# LPC_1.net
KiCad netlist of a schematic drawn in EAGLE
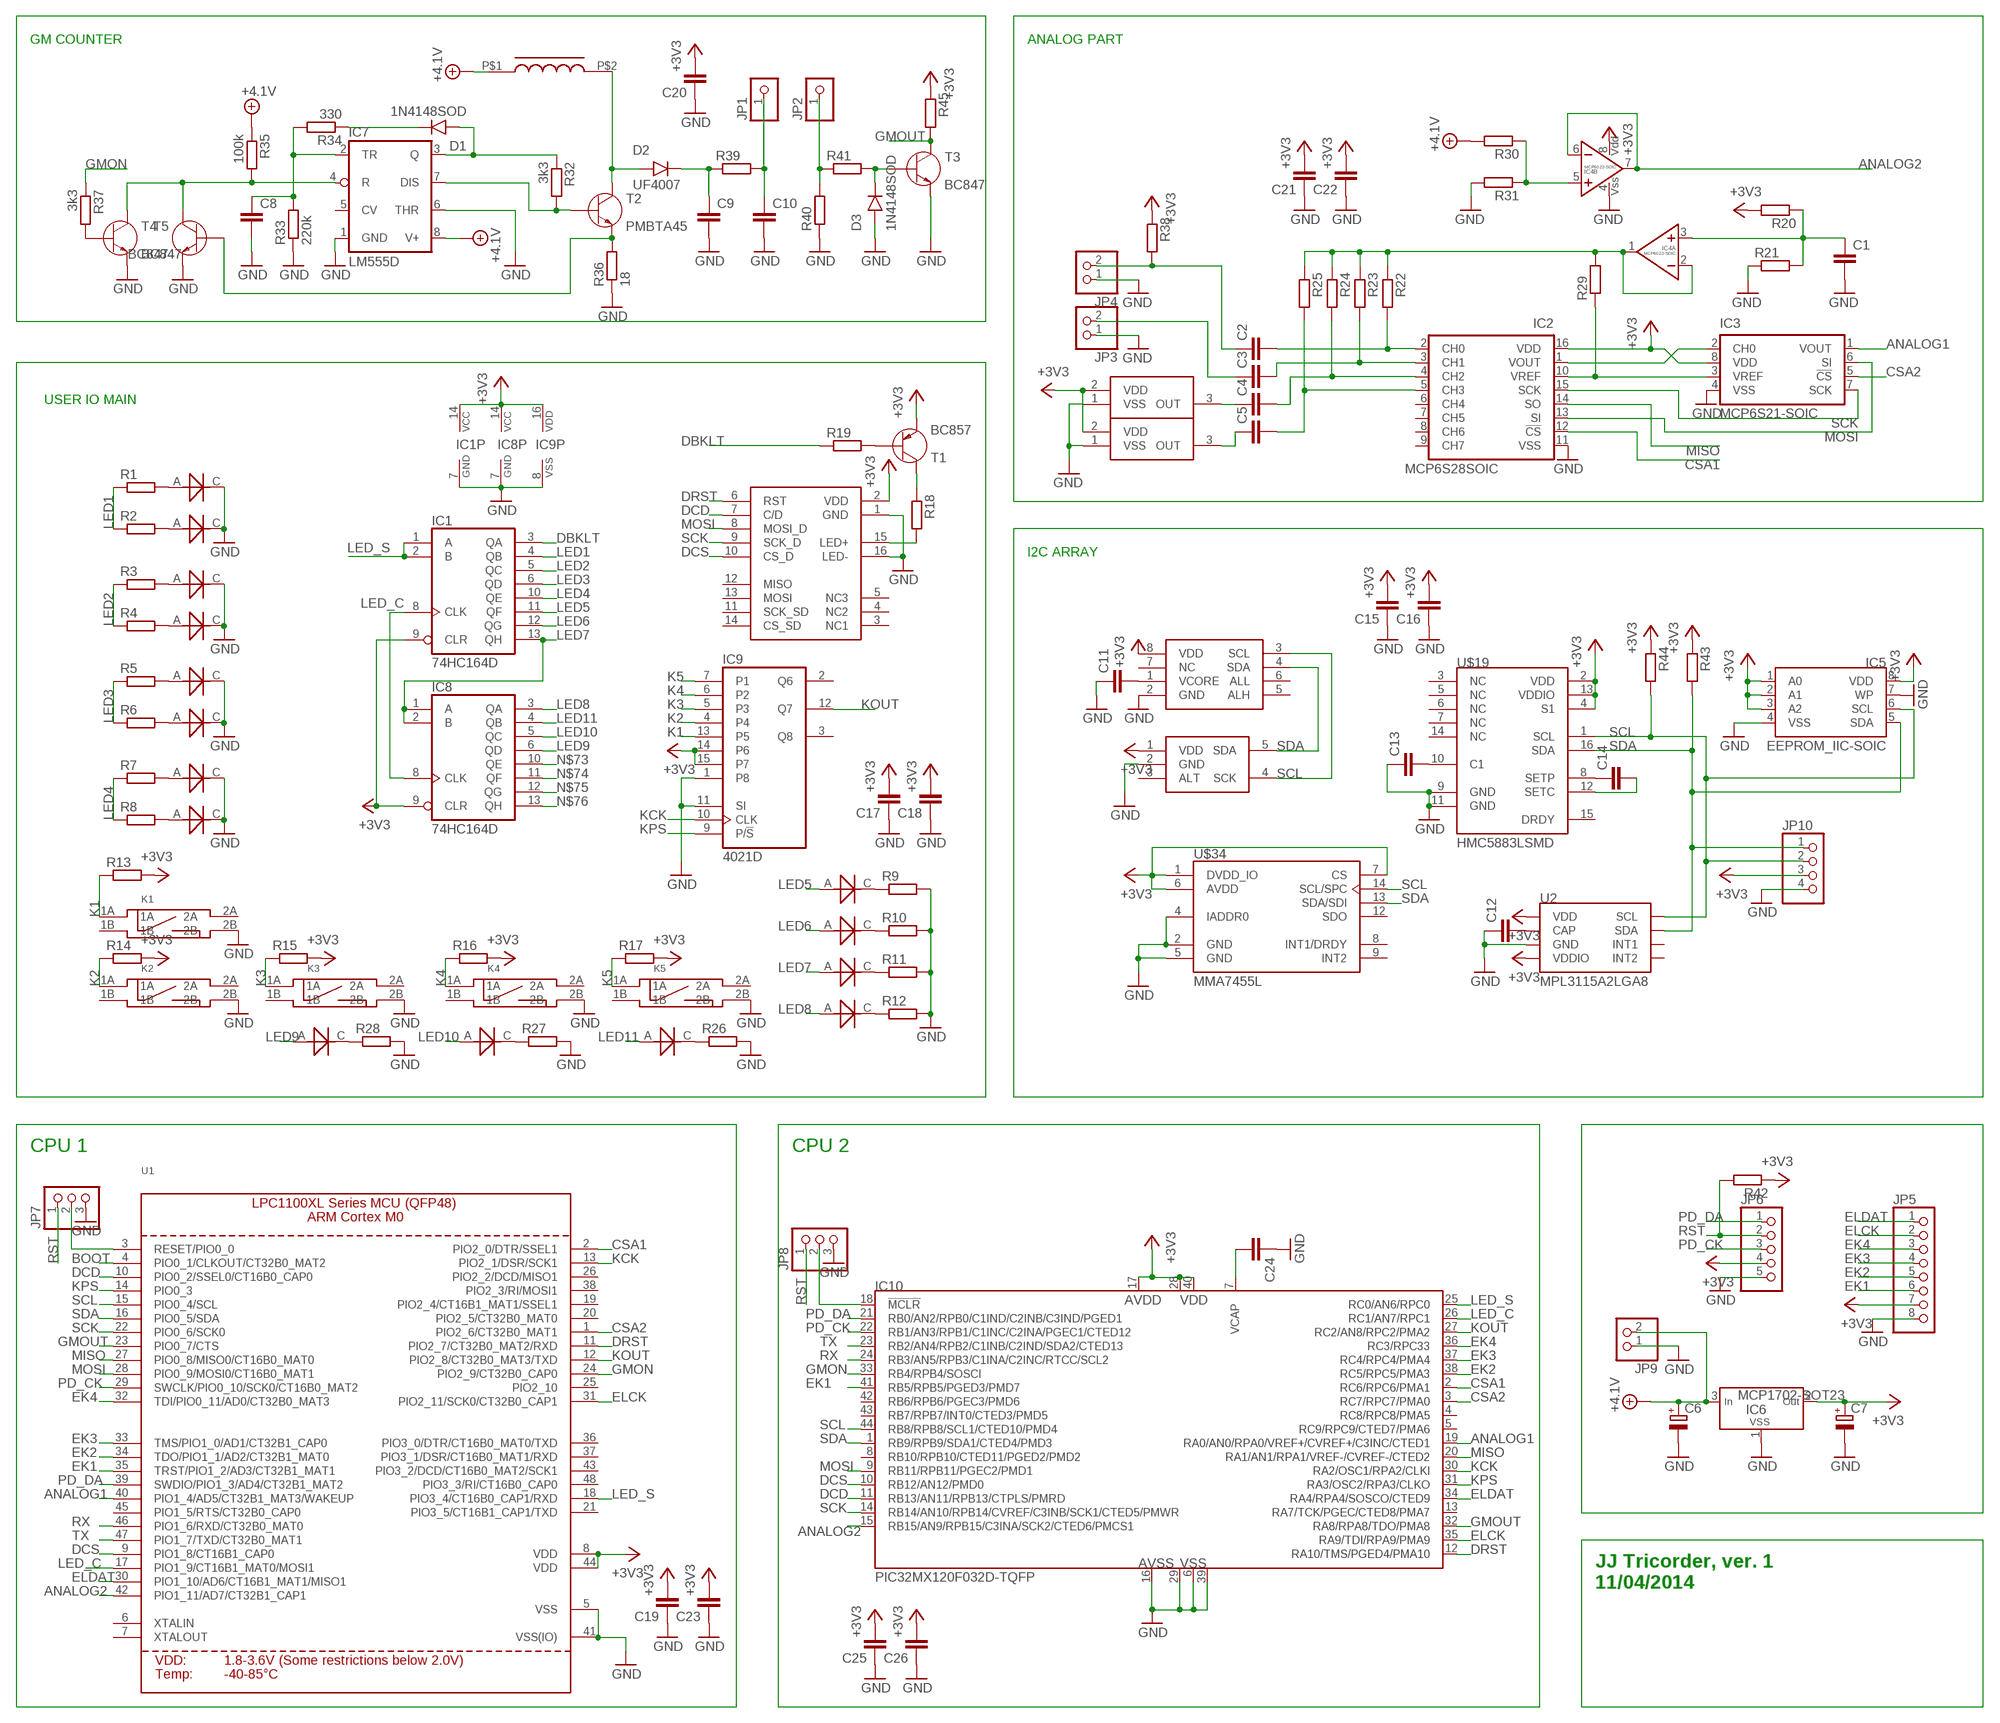
[diagram p0: schematic, sheet 1]

(export (version "E")
  (design (tool "Eeschema 10.0.6"))
  (components
    (comp (ref "C1")
      (value "C_0806")
      (footprint "eagle-import:R0805")
      (libsource (lib "eagle-import") (part "C_0806"))
    )
    (comp (ref "C2")
      (value "C_1206")
      (footprint "eagle-import:R1206")
      (libsource (lib "eagle-import") (part "C_1206"))
    )
    (comp (ref "C3")
      (value "C_1206")
      (footprint "eagle-import:R1206")
      (libsource (lib "eagle-import") (part "C_1206"))
    )
    (comp (ref "C4")
      (value "C_1206")
      (footprint "eagle-import:R1206")
      (libsource (lib "eagle-import") (part "C_1206"))
    )
    (comp (ref "C5")
      (value "C_1206")
      (footprint "eagle-import:R1206")
      (libsource (lib "eagle-import") (part "C_1206"))
    )
    (comp (ref "C6")
      (value "CPOL-EUSMCA")
      (footprint "eagle-import:SMC_A")
      (libsource (lib "eagle-import") (part "CPOL-EUSMCA"))
    )
    (comp (ref "C7")
      (value "CPOL-EUSMCA")
      (footprint "eagle-import:SMC_A")
      (libsource (lib "eagle-import") (part "CPOL-EUSMCA"))
    )
    (comp (ref "C8")
      (value "C_0806")
      (footprint "eagle-import:R0805")
      (libsource (lib "eagle-import") (part "C_0806"))
    )
    (comp (ref "C9")
      (value "C_1206")
      (footprint "eagle-import:R1206")
      (libsource (lib "eagle-import") (part "C_1206"))
    )
    (comp (ref "C10")
      (value "C_1206")
      (footprint "eagle-import:R1206")
      (libsource (lib "eagle-import") (part "C_1206"))
    )
    (comp (ref "C11")
      (value "C_0806")
      (footprint "eagle-import:R0805")
      (libsource (lib "eagle-import") (part "C_0806"))
    )
    (comp (ref "C12")
      (value "C_0806")
      (footprint "eagle-import:R0805")
      (libsource (lib "eagle-import") (part "C_0806"))
    )
    (comp (ref "C13")
      (value "C_0806")
      (footprint "eagle-import:R0805")
      (libsource (lib "eagle-import") (part "C_0806"))
    )
    (comp (ref "C14")
      (value "C_0806")
      (footprint "eagle-import:R0805")
      (libsource (lib "eagle-import") (part "C_0806"))
    )
    (comp (ref "C15")
      (value "C_0806")
      (footprint "eagle-import:R0805")
      (libsource (lib "eagle-import") (part "C_0806"))
    )
    (comp (ref "C16")
      (value "C_0806")
      (footprint "eagle-import:R0805")
      (libsource (lib "eagle-import") (part "C_0806"))
    )
    (comp (ref "C17")
      (value "C_0806")
      (footprint "eagle-import:R0805")
      (libsource (lib "eagle-import") (part "C_0806"))
    )
    (comp (ref "C18")
      (value "C_0806")
      (footprint "eagle-import:R0805")
      (libsource (lib "eagle-import") (part "C_0806"))
    )
    (comp (ref "C19")
      (value "C_0806")
      (footprint "eagle-import:R0805")
      (libsource (lib "eagle-import") (part "C_0806"))
    )
    (comp (ref "C20")
      (value "C_0806")
      (footprint "eagle-import:R0805")
      (libsource (lib "eagle-import") (part "C_0806"))
    )
    (comp (ref "C21")
      (value "C_0806")
      (footprint "eagle-import:R0805")
      (libsource (lib "eagle-import") (part "C_0806"))
    )
    (comp (ref "C22")
      (value "C_0806")
      (footprint "eagle-import:R0805")
      (libsource (lib "eagle-import") (part "C_0806"))
    )
    (comp (ref "C23")
      (value "C_0806")
      (footprint "eagle-import:R0805")
      (libsource (lib "eagle-import") (part "C_0806"))
    )
    (comp (ref "C24")
      (value "C_0806")
      (footprint "eagle-import:R0805")
      (libsource (lib "eagle-import") (part "C_0806"))
    )
    (comp (ref "C25")
      (value "C_0806")
      (footprint "eagle-import:R0805")
      (libsource (lib "eagle-import") (part "C_0806"))
    )
    (comp (ref "C26")
      (value "C_0806")
      (footprint "eagle-import:R0805")
      (libsource (lib "eagle-import") (part "C_0806"))
    )
    (comp (ref "D1")
      (value "1N4148SOD")
      (footprint "eagle-import:SOD-80")
      (libsource (lib "eagle-import") (part "1N4148SOD"))
    )
    (comp (ref "D2")
      (value "UF4007")
      (footprint "eagle-import:SM-1")
      (libsource (lib "eagle-import") (part "1N4007-SM"))
    )
    (comp (ref "D3")
      (value "1N4148SOD")
      (footprint "eagle-import:SOD-80")
      (libsource (lib "eagle-import") (part "1N4148SOD"))
    )
    (comp (ref "IC1")
      (value "74HC164D")
      (footprint "eagle-import:SO14")
      (libsource (lib "eagle-import") (part "74164DHC"))
    )
    (comp (ref "IC2")
      (value "MCP6S28SOIC")
      (footprint "eagle-import:SO-16")
      (libsource (lib "eagle-import") (part "MCP6S28SOIC"))
    )
    (comp (ref "IC3")
      (value "MCP6S21-SOIC")
      (footprint "eagle-import:SO-08")
      (libsource (lib "eagle-import") (part "MCP6S21-SOIC"))
    )
    (comp (ref "IC4")
      (value "MCP6022-SOIC")
      (footprint "eagle-import:SO-08")
      (libsource (lib "eagle-import") (part "MCP6022-SOIC"))
    )
    (comp (ref "IC5")
      (value "EEPROM_IIC-SOIC")
      (footprint "eagle-import:SO-08")
      (libsource (lib "eagle-import") (part "EEPROM_IIC-SOIC"))
    )
    (comp (ref "IC6")
      (value "MCP1702-SOT23")
      (footprint "eagle-import:SOT23")
      (libsource (lib "eagle-import") (part "MCP1702-SOT23"))
    )
    (comp (ref "IC7")
      (value "LM555D")
      (footprint "eagle-import:SO08")
      (libsource (lib "eagle-import") (part "555DLM"))
    )
    (comp (ref "IC8")
      (value "74HC164D")
      (footprint "eagle-import:SO14")
      (libsource (lib "eagle-import") (part "74164DHC"))
    )
    (comp (ref "IC9")
      (value "4021D")
      (footprint "eagle-import:SO16")
      (libsource (lib "eagle-import") (part "4021D"))
    )
    (comp (ref "IC10")
      (value "PIC32MX120F032D-TQFP")
      (footprint "eagle-import:TQFP44")
      (libsource (lib "eagle-import") (part "PIC32MX120F032D-TQFP"))
    )
    (comp (ref "JP1")
      (value "PINHD-1X1")
      (footprint "eagle-import:1X01")
      (libsource (lib "eagle-import") (part "PINHD-1X1"))
    )
    (comp (ref "JP2")
      (value "PINHD-1X1")
      (footprint "eagle-import:1X01")
      (libsource (lib "eagle-import") (part "PINHD-1X1"))
    )
    (comp (ref "JP3")
      (value "PINHD-1X02_2.54")
      (footprint "eagle-import:1X02")
      (libsource (lib "eagle-import") (part "PINHD-1X02_2.54"))
    )
    (comp (ref "JP4")
      (value "PINHD-1X02_2.54")
      (footprint "eagle-import:1X02")
      (libsource (lib "eagle-import") (part "PINHD-1X02_2.54"))
    )
    (comp (ref "JP5")
      (value "PINHD-1X08_2.54-S")
      (footprint "eagle-import:1X08-S")
      (libsource (lib "eagle-import") (part "PINHD-1X08_2.54-S"))
    )
    (comp (ref "JP6")
      (value "PINHD-1X05_2.54-90°-S")
      (footprint "eagle-import:1X05_90-S")
      (libsource (lib "eagle-import") (part "PINHD-1X05_2.54-90°-S"))
    )
    (comp (ref "JP7")
      (value "PINHD-1X03_2.00")
      (footprint "eagle-import:1X03M")
      (libsource (lib "eagle-import") (part "PINHD-1X03_2.00"))
    )
    (comp (ref "JP8")
      (value "PINHD-1X03_2.00")
      (footprint "eagle-import:1X03M")
      (libsource (lib "eagle-import") (part "PINHD-1X03_2.00"))
    )
    (comp (ref "JP9")
      (value "PINHD-1X02_2.54-90°")
      (footprint "eagle-import:1X02_90")
      (libsource (lib "eagle-import") (part "PINHD-1X02_2.54-90°"))
    )
    (comp (ref "JP10")
      (value "PINHD-1X04_2.00")
      (footprint "eagle-import:1X04M")
      (libsource (lib "eagle-import") (part "PINHD-1X04_2.00"))
    )
    (comp (ref "K1")
      (value "SWITCH_BD_B")
      (footprint "eagle-import:SW_SMD2")
      (libsource (lib "eagle-import") (part "SWITCH_BD_B"))
    )
    (comp (ref "K2")
      (value "SWITCH_BD_B")
      (footprint "eagle-import:SW_SMD2")
      (libsource (lib "eagle-import") (part "SWITCH_BD_B"))
    )
    (comp (ref "K3")
      (value "SWITCH_BD_B")
      (footprint "eagle-import:SW_SMD2")
      (libsource (lib "eagle-import") (part "SWITCH_BD_B"))
    )
    (comp (ref "K4")
      (value "SWITCH_BD_B")
      (footprint "eagle-import:SW_SMD2")
      (libsource (lib "eagle-import") (part "SWITCH_BD_B"))
    )
    (comp (ref "K5")
      (value "SWITCH_BD_B")
      (footprint "eagle-import:SW_SMD2")
      (libsource (lib "eagle-import") (part "SWITCH_BD_B"))
    )
    (comp (ref "R1")
      (value "R_0805")
      (footprint "eagle-import:R0805")
      (libsource (lib "eagle-import") (part "R_0805"))
    )
    (comp (ref "R2")
      (value "R_0805")
      (footprint "eagle-import:R0805")
      (libsource (lib "eagle-import") (part "R_0805"))
    )
    (comp (ref "R3")
      (value "R_0805")
      (footprint "eagle-import:R0805")
      (libsource (lib "eagle-import") (part "R_0805"))
    )
    (comp (ref "R4")
      (value "R_0805")
      (footprint "eagle-import:R0805")
      (libsource (lib "eagle-import") (part "R_0805"))
    )
    (comp (ref "R5")
      (value "R_0805")
      (footprint "eagle-import:R0805")
      (libsource (lib "eagle-import") (part "R_0805"))
    )
    (comp (ref "R6")
      (value "R_0805")
      (footprint "eagle-import:R0805")
      (libsource (lib "eagle-import") (part "R_0805"))
    )
    (comp (ref "R7")
      (value "R_0805")
      (footprint "eagle-import:R0805")
      (libsource (lib "eagle-import") (part "R_0805"))
    )
    (comp (ref "R8")
      (value "R_0805")
      (footprint "eagle-import:R0805")
      (libsource (lib "eagle-import") (part "R_0805"))
    )
    (comp (ref "R9")
      (value "R_0805")
      (footprint "eagle-import:R0805")
      (libsource (lib "eagle-import") (part "R_0805"))
    )
    (comp (ref "R10")
      (value "R_0805")
      (footprint "eagle-import:R0805")
      (libsource (lib "eagle-import") (part "R_0805"))
    )
    (comp (ref "R11")
      (value "R_0805")
      (footprint "eagle-import:R0805")
      (libsource (lib "eagle-import") (part "R_0805"))
    )
    (comp (ref "R12")
      (value "R_0805")
      (footprint "eagle-import:R0805")
      (libsource (lib "eagle-import") (part "R_0805"))
    )
    (comp (ref "R13")
      (value "R_0805")
      (footprint "eagle-import:R0805")
      (libsource (lib "eagle-import") (part "R_0805"))
    )
    (comp (ref "R14")
      (value "R_0805")
      (footprint "eagle-import:R0805")
      (libsource (lib "eagle-import") (part "R_0805"))
    )
    (comp (ref "R15")
      (value "R_0805")
      (footprint "eagle-import:R0805")
      (libsource (lib "eagle-import") (part "R_0805"))
    )
    (comp (ref "R16")
      (value "R_0805")
      (footprint "eagle-import:R0805")
      (libsource (lib "eagle-import") (part "R_0805"))
    )
    (comp (ref "R17")
      (value "R_0805")
      (footprint "eagle-import:R0805")
      (libsource (lib "eagle-import") (part "R_0805"))
    )
    (comp (ref "R18")
      (value "R_0805")
      (footprint "eagle-import:R0805")
      (libsource (lib "eagle-import") (part "R_0805"))
    )
    (comp (ref "R19")
      (value "R_0805")
      (footprint "eagle-import:R0805")
      (libsource (lib "eagle-import") (part "R_0805"))
    )
    (comp (ref "R20")
      (value "R_0805")
      (footprint "eagle-import:R0805")
      (libsource (lib "eagle-import") (part "R_0805"))
    )
    (comp (ref "R21")
      (value "R_0805")
      (footprint "eagle-import:R0805")
      (libsource (lib "eagle-import") (part "R_0805"))
    )
    (comp (ref "R22")
      (value "R_0805")
      (footprint "eagle-import:R0805")
      (libsource (lib "eagle-import") (part "R_0805"))
    )
    (comp (ref "R23")
      (value "R_0805")
      (footprint "eagle-import:R0805")
      (libsource (lib "eagle-import") (part "R_0805"))
    )
    (comp (ref "R24")
      (value "R_0805")
      (footprint "eagle-import:R0805")
      (libsource (lib "eagle-import") (part "R_0805"))
    )
    (comp (ref "R25")
      (value "R_0805")
      (footprint "eagle-import:R0805")
      (libsource (lib "eagle-import") (part "R_0805"))
    )
    (comp (ref "R26")
      (value "R_0805")
      (footprint "eagle-import:R0805")
      (libsource (lib "eagle-import") (part "R_0805"))
    )
    (comp (ref "R27")
      (value "R_0805")
      (footprint "eagle-import:R0805")
      (libsource (lib "eagle-import") (part "R_0805"))
    )
    (comp (ref "R28")
      (value "R_0805")
      (footprint "eagle-import:R0805")
      (libsource (lib "eagle-import") (part "R_0805"))
    )
    (comp (ref "R29")
      (value "R_0805")
      (footprint "eagle-import:R0805")
      (libsource (lib "eagle-import") (part "R_0805"))
    )
    (comp (ref "R30")
      (value "R_0805")
      (footprint "eagle-import:R0805")
      (libsource (lib "eagle-import") (part "R_0805"))
    )
    (comp (ref "R31")
      (value "R_0805")
      (footprint "eagle-import:R0805")
      (libsource (lib "eagle-import") (part "R_0805"))
    )
    (comp (ref "R32")
      (value "3k3")
      (footprint "eagle-import:R0805")
      (libsource (lib "eagle-import") (part "R_0805"))
    )
    (comp (ref "R33")
      (value "220k")
      (footprint "eagle-import:R0805")
      (libsource (lib "eagle-import") (part "R_0805"))
    )
    (comp (ref "R34")
      (value "330")
      (footprint "eagle-import:R0805")
      (libsource (lib "eagle-import") (part "R_0805"))
    )
    (comp (ref "R35")
      (value "100k")
      (footprint "eagle-import:R0805")
      (libsource (lib "eagle-import") (part "R_0805"))
    )
    (comp (ref "R36")
      (value "18")
      (footprint "eagle-import:R0805")
      (libsource (lib "eagle-import") (part "R_0805"))
    )
    (comp (ref "R37")
      (value "3k3")
      (footprint "eagle-import:R0805")
      (libsource (lib "eagle-import") (part "R_0805"))
    )
    (comp (ref "R38")
      (value "R_0805")
      (footprint "eagle-import:R0805")
      (libsource (lib "eagle-import") (part "R_0805"))
    )
    (comp (ref "R39")
      (value "R_1206")
      (footprint "eagle-import:R1206")
      (libsource (lib "eagle-import") (part "R_1206"))
    )
    (comp (ref "R40")
      (value "R_1206")
      (footprint "eagle-import:R1206")
      (libsource (lib "eagle-import") (part "R_1206"))
    )
    (comp (ref "R41")
      (value "R_0805")
      (footprint "eagle-import:R0805")
      (libsource (lib "eagle-import") (part "R_0805"))
    )
    (comp (ref "R42")
      (value "R_0805")
      (footprint "eagle-import:R0805")
      (libsource (lib "eagle-import") (part "R_0805"))
    )
    (comp (ref "R43")
      (value "R_0805")
      (footprint "eagle-import:R0805")
      (libsource (lib "eagle-import") (part "R_0805"))
    )
    (comp (ref "R44")
      (value "R_0805")
      (footprint "eagle-import:R0805")
      (libsource (lib "eagle-import") (part "R_0805"))
    )
    (comp (ref "R45")
      (value "R_0805")
      (footprint "eagle-import:R0805")
      (libsource (lib "eagle-import") (part "R_0805"))
    )
    (comp (ref "T1")
      (value "BC857")
      (footprint "eagle-import:SOT23")
      (libsource (lib "eagle-import") (part "BC857"))
    )
    (comp (ref "T2")
      (value "PMBTA45")
      (footprint "eagle-import:SOT23")
      (libsource (lib "eagle-import") (part "BC847"))
    )
    (comp (ref "T3")
      (value "BC847")
      (footprint "eagle-import:SOT23")
      (libsource (lib "eagle-import") (part "BC847"))
    )
    (comp (ref "T4")
      (value "BC847")
      (footprint "eagle-import:SOT23")
      (libsource (lib "eagle-import") (part "BC847"))
    )
    (comp (ref "T5")
      (value "BC847")
      (footprint "eagle-import:SOT23")
      (libsource (lib "eagle-import") (part "BC847"))
    )
    (comp (ref "U$1")
      (value "LED5X2")
      (footprint "eagle-import:LED_5X2")
      (libsource (lib "eagle-import") (part "LED5X2"))
    )
    (comp (ref "U$2")
      (value "LED5X5")
      (footprint "eagle-import:LED_5X5")
      (libsource (lib "eagle-import") (part "LED5X5"))
    )
    (comp (ref "U$3")
      (value "DISP_TFT_18")
      (footprint "eagle-import:DSIP_TFT_18")
      (libsource (lib "eagle-import") (part "DISP_TFT_18"))
    )
    (comp (ref "U$4")
      (value "LED5X5")
      (footprint "eagle-import:LED_5X5")
      (libsource (lib "eagle-import") (part "LED5X5"))
    )
    (comp (ref "U$5")
      (value "LED5X5")
      (footprint "eagle-import:LED_5X5")
      (libsource (lib "eagle-import") (part "LED5X5"))
    )
    (comp (ref "U$6")
      (value "LED5X5")
      (footprint "eagle-import:LED_5X5")
      (libsource (lib "eagle-import") (part "LED5X5"))
    )
    (comp (ref "U$7")
      (value "LED5X5")
      (footprint "eagle-import:LED_5X5")
      (libsource (lib "eagle-import") (part "LED5X5"))
    )
    (comp (ref "U$8")
      (value "LED5X5")
      (footprint "eagle-import:LED_5X5")
      (libsource (lib "eagle-import") (part "LED5X5"))
    )
    (comp (ref "U$9")
      (value "LED5X5")
      (footprint "eagle-import:LED_5X5")
      (libsource (lib "eagle-import") (part "LED5X5"))
    )
    (comp (ref "U$10")
      (value "LED5X5")
      (footprint "eagle-import:LED_5X5")
      (libsource (lib "eagle-import") (part "LED5X5"))
    )
    (comp (ref "U$11")
      (value "LED5X2")
      (footprint "eagle-import:LED_5X2")
      (libsource (lib "eagle-import") (part "LED5X2"))
    )
    (comp (ref "U$12")
      (value "LED5X2")
      (footprint "eagle-import:LED_5X2")
      (libsource (lib "eagle-import") (part "LED5X2"))
    )
    (comp (ref "U$13")
      (value "LED5X2")
      (footprint "eagle-import:LED_5X2")
      (libsource (lib "eagle-import") (part "LED5X2"))
    )
    (comp (ref "U$14")
      (value "LED5X2")
      (footprint "eagle-import:LED_5X2")
      (libsource (lib "eagle-import") (part "LED5X2"))
    )
    (comp (ref "U$15")
      (value "LED5X2")
      (footprint "eagle-import:LED_5X2")
      (libsource (lib "eagle-import") (part "LED5X2"))
    )
    (comp (ref "U$16")
      (value "LED5X2")
      (footprint "eagle-import:LED_5X2")
      (libsource (lib "eagle-import") (part "LED5X2"))
    )
    (comp (ref "U$17")
      (value "HIH-6130")
      (footprint "eagle-import:SO8")
      (libsource (lib "eagle-import") (part "HIH-6130"))
    )
    (comp (ref "U$18")
      (value "MCP9800")
      (footprint "eagle-import:SOT23-5")
      (libsource (lib "eagle-import") (part "MCP9800"))
    )
    (comp (ref "U$19")
      (value "HMC5883LSMD")
      (footprint "eagle-import:16LPCC")
      (libsource (lib "eagle-import") (part "HMC5883LSMD"))
    )
    (comp (ref "U$20")
      (value "IND_DL22")
      (footprint "eagle-import:IND_DL22")
      (libsource (lib "eagle-import") (part "IND_DL22"))
    )
    (comp (ref "U$21")
      (value "TSL252")
      (footprint "eagle-import:TSL252")
      (libsource (lib "eagle-import") (part "TSL252"))
    )
    (comp (ref "U$22")
      (value "TSL252")
      (footprint "eagle-import:TSL252")
      (libsource (lib "eagle-import") (part "TSL252"))
    )
    (comp (ref "U$34")
      (value "MMA7455L")
      (footprint "eagle-import:LGA14")
      (libsource (lib "eagle-import") (part "MMA7455L"))
    )
    (comp (ref "U1")
      (value "LPC1113/4/5_QFP48_XLSERIES")
      (footprint "eagle-import:LQFP48")
      (libsource (lib "eagle-import") (part "LPC1113/4/5_QFP48_XLSERIES"))
    )
    (comp (ref "U2")
      (value "MPL3115A2LGA8")
      (footprint "eagle-import:LGA8")
      (libsource (lib "eagle-import") (part "MPL3115A2LGA8"))
    )
  )
  (nets
    (net (code "1") (name "+3V3") (class "Default")
      (node (ref "C15") (pin "2") (pinfunction "2_2") (pintype "passive"))
      (node (ref "C16") (pin "2") (pinfunction "2_2") (pintype "passive"))
      (node (ref "C17") (pin "2") (pinfunction "2_2") (pintype "passive"))
      (node (ref "C18") (pin "2") (pinfunction "2_2") (pintype "passive"))
      (node (ref "C19") (pin "2") (pinfunction "2_2") (pintype "passive"))
      (node (ref "C20") (pin "2") (pinfunction "2_2") (pintype "passive"))
      (node (ref "C21") (pin "2") (pinfunction "2_2") (pintype "passive"))
      (node (ref "C22") (pin "2") (pinfunction "2_2") (pintype "passive"))
      (node (ref "C23") (pin "2") (pinfunction "2_2") (pintype "passive"))
      (node (ref "C25") (pin "2") (pinfunction "2_2") (pintype "passive"))
      (node (ref "C26") (pin "2") (pinfunction "2_2") (pintype "passive"))
      (node (ref "C7") (pin "+") (pinfunction "+_+") (pintype "passive"))
      (node (ref "IC1") (pin "14") (pinfunction "VCC_14") (pintype "power_in"))
      (node (ref "IC1") (pin "9") (pinfunction "CLR_9") (pintype "input"))
      (node (ref "IC10") (pin "17") (pinfunction "AVDD_17") (pintype "power_in"))
      (node (ref "IC10") (pin "28") (pinfunction "VDD_28") (pintype "power_in"))
      (node (ref "IC10") (pin "40") (pinfunction "VDD2_40") (pintype "power_in"))
      (node (ref "IC2") (pin "16") (pinfunction "VDD_16") (pintype "power_in"))
      (node (ref "IC3") (pin "8") (pinfunction "VDD_8") (pintype "power_in"))
      (node (ref "IC4") (pin "8") (pinfunction "VDD_8") (pintype "power_in"))
      (node (ref "IC5") (pin "1") (pinfunction "A0_1") (pintype "input"))
      (node (ref "IC5") (pin "2") (pinfunction "A1_2") (pintype "input"))
      (node (ref "IC5") (pin "3") (pinfunction "A2_3") (pintype "input"))
      (node (ref "IC5") (pin "8") (pinfunction "VDD_8") (pintype "power_in"))
      (node (ref "IC6") (pin "2") (pinfunction "OUT_2") (pintype "output"))
      (node (ref "IC8") (pin "14") (pinfunction "VCC_14") (pintype "power_in"))
      (node (ref "IC8") (pin "9") (pinfunction "CLR_9") (pintype "input"))
      (node (ref "IC9") (pin "14") (pinfunction "P6_14") (pintype "input"))
      (node (ref "IC9") (pin "15") (pinfunction "P7_15") (pintype "input"))
      (node (ref "IC9") (pin "16") (pinfunction "VDD_16") (pintype "power_in"))
      (node (ref "JP10") (pin "3") (pinfunction "3_3") (pintype "passive"))
      (node (ref "JP5") (pin "7") (pinfunction "7_7") (pintype "passive"))
      (node (ref "JP6") (pin "4") (pinfunction "4_4") (pintype "passive"))
      (node (ref "R13") (pin "2") (pinfunction "2_2") (pintype "passive"))
      (node (ref "R14") (pin "2") (pinfunction "2_2") (pintype "passive"))
      (node (ref "R15") (pin "2") (pinfunction "2_2") (pintype "passive"))
      (node (ref "R16") (pin "2") (pinfunction "2_2") (pintype "passive"))
      (node (ref "R17") (pin "2") (pinfunction "2_2") (pintype "passive"))
      (node (ref "R20") (pin "2") (pinfunction "2_2") (pintype "passive"))
      (node (ref "R38") (pin "1") (pinfunction "1_1") (pintype "passive"))
      (node (ref "R42") (pin "1") (pinfunction "1_1") (pintype "passive"))
      (node (ref "R43") (pin "1") (pinfunction "1_1") (pintype "passive"))
      (node (ref "R44") (pin "1") (pinfunction "1_1") (pintype "passive"))
      (node (ref "R45") (pin "1") (pinfunction "1_1") (pintype "passive"))
      (node (ref "T1") (pin "3") (pinfunction "C_3") (pintype "passive"))
      (node (ref "U$17") (pin "8") (pinfunction "VDD_8") (pintype "bidirectional"))
      (node (ref "U$18") (pin "1") (pinfunction "VDD_1") (pintype "bidirectional"))
      (node (ref "U$19") (pin "13") (pinfunction "VDDIO_13") (pintype "bidirectional"))
      (node (ref "U$19") (pin "2") (pinfunction "VDD_2") (pintype "bidirectional"))
      (node (ref "U$19") (pin "4") (pinfunction "S1_4") (pintype "bidirectional"))
      (node (ref "U$21") (pin "2") (pinfunction "VDD_2") (pintype "bidirectional"))
      (node (ref "U$22") (pin "2") (pinfunction "VDD_2") (pintype "bidirectional"))
      (node (ref "U$3") (pin "2") (pinfunction "VDD_2") (pintype "bidirectional"))
      (node (ref "U$34") (pin "1") (pinfunction "DVDD_IO_1") (pintype "power_in"))
      (node (ref "U$34") (pin "6") (pinfunction "AVDD_6") (pintype "power_in"))
      (node (ref "U$34") (pin "7") (pinfunction "CS_7") (pintype "input"))
      (node (ref "U1") (pin "44") (pinfunction "VDD_44") (pintype "power_in"))
      (node (ref "U1") (pin "8") (pinfunction "VDD_8") (pintype "power_in"))
      (node (ref "U2") (pin "1") (pinfunction "VDD_1") (pintype "power_in"))
      (node (ref "U2") (pin "4") (pinfunction "VDDIO_4") (pintype "power_in"))
    )
    (net (code "2") (name "+4.1V") (class "Default")
      (node (ref "C6") (pin "+") (pinfunction "+_+") (pintype "passive"))
      (node (ref "IC6") (pin "3") (pinfunction "IN_3") (pintype "input"))
      (node (ref "IC7") (pin "8") (pinfunction "V+_8") (pintype "power_in"))
      (node (ref "JP9") (pin "2") (pinfunction "2_2") (pintype "passive"))
      (node (ref "R30") (pin "2") (pinfunction "2_2") (pintype "passive"))
      (node (ref "R35") (pin "1") (pinfunction "1_1") (pintype "passive"))
      (node (ref "U$20") (pin "P$1") (pinfunction "P$1_P$1") (pintype "bidirectional"))
    )
    (net (code "3") (name "/ANALOG1") (class "Default")
      (node (ref "IC10") (pin "19") (pinfunction "RA0/AN0/RPA0/VREF+/CVREF+/C3INC/CTED1_19") (pintype "bidirectional"))
      (node (ref "IC3") (pin "1") (pinfunction "VOUT_1") (pintype "bidirectional"))
      (node (ref "U1") (pin "40") (pinfunction "PIO1_4/AD5/CT32B1_MAT3/WAKEUP_40") (pintype "bidirectional"))
    )
    (net (code "4") (name "/ANALOG2") (class "Default")
      (node (ref "IC10") (pin "15") (pinfunction "RB15/AN9/RPB15/C3INA/SCK2/CTED6/PMCS1_15") (pintype "bidirectional"))
      (node (ref "IC4") (pin "6") (pinfunction "IN-_6") (pintype "input"))
      (node (ref "IC4") (pin "7") (pinfunction "VYSTUP_7") (pintype "output"))
      (node (ref "U1") (pin "42") (pinfunction "PIO1_11/AD7/CT32B1_CAP1_42") (pintype "bidirectional"))
    )
    (net (code "5") (name "/BOOT") (class "Default")
      (node (ref "U1") (pin "4") (pinfunction "PIO0_1/CLKOUT/CT32B0_MAT2_4") (pintype "bidirectional"))
    )
    (net (code "6") (name "/CSA1") (class "Default")
      (node (ref "IC10") (pin "2") (pinfunction "RC6/RPC6/PMA1_2") (pintype "bidirectional"))
      (node (ref "IC2") (pin "12") (pinfunction "~{CS}_12") (pintype "bidirectional"))
      (node (ref "U1") (pin "2") (pinfunction "PIO2_0/DTR/SSEL1_2") (pintype "bidirectional"))
    )
    (net (code "7") (name "/CSA2") (class "Default")
      (node (ref "IC10") (pin "3") (pinfunction "RC7/RPC7/PMA0_3") (pintype "bidirectional"))
      (node (ref "IC3") (pin "5") (pinfunction "~{CS}_5") (pintype "bidirectional"))
      (node (ref "U1") (pin "1") (pinfunction "PIO2_6/CT32B0_MAT1_1") (pintype "bidirectional"))
    )
    (net (code "8") (name "/DBKLT") (class "Default")
      (node (ref "IC1") (pin "3") (pinfunction "QA_3") (pintype "output"))
      (node (ref "R19") (pin "1") (pinfunction "1_1") (pintype "passive"))
    )
    (net (code "9") (name "/DCD") (class "Default")
      (node (ref "IC10") (pin "11") (pinfunction "RB13/AN11/RPB13/CTPLS/PMRD_11") (pintype "bidirectional"))
      (node (ref "U$3") (pin "7") (pinfunction "C/D_7") (pintype "bidirectional"))
      (node (ref "U1") (pin "10") (pinfunction "PIO0_2/SSEL0/CT16B0_CAP0_10") (pintype "bidirectional"))
    )
    (net (code "10") (name "/DCS") (class "Default")
      (node (ref "IC10") (pin "10") (pinfunction "RB12/AN12/PMD0_10") (pintype "bidirectional"))
      (node (ref "U$3") (pin "10") (pinfunction "CS_D_10") (pintype "bidirectional"))
      (node (ref "U1") (pin "9") (pinfunction "PIO1_8/CT16B1_CAP0_9") (pintype "bidirectional"))
    )
    (net (code "11") (name "/DRST") (class "Default")
      (node (ref "IC10") (pin "12") (pinfunction "RA10/TMS/PGED4/PMA10_12") (pintype "bidirectional"))
      (node (ref "U$3") (pin "6") (pinfunction "RST_6") (pintype "bidirectional"))
      (node (ref "U1") (pin "11") (pinfunction "PIO2_7/CT32B0_MAT2/RXD_11") (pintype "bidirectional"))
    )
    (net (code "12") (name "/EK1") (class "Default")
      (node (ref "IC10") (pin "41") (pinfunction "RB5/RPB5/PGED3/PMD7_41") (pintype "bidirectional"))
      (node (ref "JP5") (pin "6") (pinfunction "6_6") (pintype "passive"))
      (node (ref "U1") (pin "35") (pinfunction "TRST/PIO1_2/AD3/CT32B1_MAT1_35") (pintype "bidirectional"))
    )
    (net (code "13") (name "/EK2") (class "Default")
      (node (ref "IC10") (pin "38") (pinfunction "RC5/RPC5/PMA3_38") (pintype "bidirectional"))
      (node (ref "JP5") (pin "5") (pinfunction "5_5") (pintype "passive"))
      (node (ref "U1") (pin "34") (pinfunction "TDO/PIO1_1/AD2/CT32B1_MAT0_34") (pintype "bidirectional"))
    )
    (net (code "14") (name "/EK3") (class "Default")
      (node (ref "IC10") (pin "37") (pinfunction "RC4/RPC4/PMA4_37") (pintype "bidirectional"))
      (node (ref "JP5") (pin "4") (pinfunction "4_4") (pintype "passive"))
      (node (ref "U1") (pin "33") (pinfunction "TMS/PIO1_0/AD1/CT32B1_CAP0_33") (pintype "bidirectional"))
    )
    (net (code "15") (name "/EK4") (class "Default")
      (node (ref "IC10") (pin "36") (pinfunction "RC3/RPC33_36") (pintype "bidirectional"))
      (node (ref "JP5") (pin "3") (pinfunction "3_3") (pintype "passive"))
      (node (ref "U1") (pin "32") (pinfunction "TDI/PIO0_11/AD0/CT32B0_MAT3_32") (pintype "bidirectional"))
    )
    (net (code "16") (name "/ELCK") (class "Default")
      (node (ref "IC10") (pin "35") (pinfunction "RA9/TDI/RPA9/PMA9_35") (pintype "bidirectional"))
      (node (ref "JP5") (pin "2") (pinfunction "2_2") (pintype "passive"))
      (node (ref "U1") (pin "31") (pinfunction "PIO2_11/SCK0/CT32B0_CAP1_31") (pintype "bidirectional"))
    )
    (net (code "17") (name "/ELDAT") (class "Default")
      (node (ref "IC10") (pin "34") (pinfunction "RA4/RPA4/SOSCO/CTED9_34") (pintype "bidirectional"))
      (node (ref "JP5") (pin "1") (pinfunction "1_1") (pintype "passive"))
      (node (ref "U1") (pin "30") (pinfunction "PIO1_10/AD6/CT16B1_MAT1/MISO1_30") (pintype "bidirectional"))
    )
    (net (code "18") (name "/GMON") (class "Default")
      (node (ref "IC10") (pin "33") (pinfunction "RB4/RPB4/SOSCI_33") (pintype "bidirectional"))
      (node (ref "R37") (pin "1") (pinfunction "1_1") (pintype "passive"))
      (node (ref "U1") (pin "24") (pinfunction "PIO2_9/CT32B0_CAP0_24") (pintype "bidirectional"))
    )
    (net (code "19") (name "/GMOUT") (class "Default")
      (node (ref "IC10") (pin "32") (pinfunction "RA8/RPA8/TDO/PMA8_32") (pintype "bidirectional"))
      (node (ref "R45") (pin "2") (pinfunction "2_2") (pintype "passive"))
      (node (ref "T3") (pin "3") (pinfunction "C_3") (pintype "passive"))
      (node (ref "U1") (pin "23") (pinfunction "PIO0_7/CTS_23") (pintype "bidirectional"))
    )
    (net (code "20") (name "/K1") (class "Default")
      (node (ref "IC9") (pin "13") (pinfunction "P5_13") (pintype "input"))
      (node (ref "K1") (pin "1A") (pinfunction "1A_1A") (pintype "bidirectional"))
      (node (ref "R13") (pin "1") (pinfunction "1_1") (pintype "passive"))
    )
    (net (code "21") (name "/K2") (class "Default")
      (node (ref "IC9") (pin "4") (pinfunction "P4_4") (pintype "input"))
      (node (ref "K2") (pin "1A") (pinfunction "1A_1A") (pintype "bidirectional"))
      (node (ref "R14") (pin "1") (pinfunction "1_1") (pintype "passive"))
    )
    (net (code "22") (name "/K3") (class "Default")
      (node (ref "IC9") (pin "5") (pinfunction "P3_5") (pintype "input"))
      (node (ref "K3") (pin "1A") (pinfunction "1A_1A") (pintype "bidirectional"))
      (node (ref "R15") (pin "1") (pinfunction "1_1") (pintype "passive"))
    )
    (net (code "23") (name "/K4") (class "Default")
      (node (ref "IC9") (pin "6") (pinfunction "P2_6") (pintype "input"))
      (node (ref "K4") (pin "1A") (pinfunction "1A_1A") (pintype "bidirectional"))
      (node (ref "R16") (pin "1") (pinfunction "1_1") (pintype "passive"))
    )
    (net (code "24") (name "/K5") (class "Default")
      (node (ref "IC9") (pin "7") (pinfunction "P1_7") (pintype "input"))
      (node (ref "K5") (pin "1A") (pinfunction "1A_1A") (pintype "bidirectional"))
      (node (ref "R17") (pin "1") (pinfunction "1_1") (pintype "passive"))
    )
    (net (code "25") (name "/KCK") (class "Default")
      (node (ref "IC10") (pin "30") (pinfunction "RA2/OSC1/RPA2/CLKI_30") (pintype "bidirectional"))
      (node (ref "IC9") (pin "10") (pinfunction "CLK_10") (pintype "input"))
      (node (ref "U1") (pin "13") (pinfunction "PIO2_1/DSR/SCK1_13") (pintype "bidirectional"))
    )
    (net (code "26") (name "/KOUT") (class "Default")
      (node (ref "IC10") (pin "27") (pinfunction "RC2/AN8/RPC2/PMA2_27") (pintype "bidirectional"))
      (node (ref "IC9") (pin "12") (pinfunction "Q7_12") (pintype "output"))
      (node (ref "U1") (pin "12") (pinfunction "PIO2_8/CT32B0_MAT3/TXD_12") (pintype "bidirectional"))
    )
    (net (code "27") (name "/KPS") (class "Default")
      (node (ref "IC10") (pin "31") (pinfunction "RA3/OSC2/RPA3/CLKO_31") (pintype "bidirectional"))
      (node (ref "IC9") (pin "9") (pinfunction "P/~{S}_9") (pintype "input"))
      (node (ref "U1") (pin "14") (pinfunction "PIO0_3_14") (pintype "bidirectional"))
    )
    (net (code "28") (name "/LED1") (class "Default")
      (node (ref "IC1") (pin "4") (pinfunction "QB_4") (pintype "output"))
      (node (ref "R1") (pin "1") (pinfunction "1_1") (pintype "passive"))
      (node (ref "R2") (pin "1") (pinfunction "1_1") (pintype "passive"))
    )
    (net (code "29") (name "/LED2") (class "Default")
      (node (ref "IC1") (pin "5") (pinfunction "QC_5") (pintype "output"))
      (node (ref "R3") (pin "1") (pinfunction "1_1") (pintype "passive"))
      (node (ref "R4") (pin "1") (pinfunction "1_1") (pintype "passive"))
    )
    (net (code "30") (name "/LED3") (class "Default")
      (node (ref "IC1") (pin "6") (pinfunction "QD_6") (pintype "output"))
      (node (ref "R5") (pin "1") (pinfunction "1_1") (pintype "passive"))
      (node (ref "R6") (pin "1") (pinfunction "1_1") (pintype "passive"))
    )
    (net (code "31") (name "/LED4") (class "Default")
      (node (ref "IC1") (pin "10") (pinfunction "QE_10") (pintype "output"))
      (node (ref "R7") (pin "1") (pinfunction "1_1") (pintype "passive"))
      (node (ref "R8") (pin "1") (pinfunction "1_1") (pintype "passive"))
    )
    (net (code "32") (name "/LED5") (class "Default")
      (node (ref "IC1") (pin "11") (pinfunction "QF_11") (pintype "output"))
      (node (ref "U$13") (pin "A") (pinfunction "A_A") (pintype "bidirectional"))
    )
    (net (code "33") (name "/LED6") (class "Default")
      (node (ref "IC1") (pin "12") (pinfunction "QG_12") (pintype "output"))
      (node (ref "U$1") (pin "A") (pinfunction "A_A") (pintype "bidirectional"))
    )
    (net (code "34") (name "/LED7") (class "Default")
      (node (ref "IC1") (pin "13") (pinfunction "QH_13") (pintype "output"))
      (node (ref "IC8") (pin "1") (pinfunction "A_1") (pintype "input"))
      (node (ref "IC8") (pin "2") (pinfunction "B_2") (pintype "input"))
      (node (ref "U$11") (pin "A") (pinfunction "A_A") (pintype "bidirectional"))
    )
    (net (code "35") (name "/LED8") (class "Default")
      (node (ref "IC8") (pin "3") (pinfunction "QA_3") (pintype "output"))
      (node (ref "U$12") (pin "A") (pinfunction "A_A") (pintype "bidirectional"))
    )
    (net (code "36") (name "/LED9") (class "Default")
      (node (ref "IC8") (pin "6") (pinfunction "QD_6") (pintype "output"))
      (node (ref "U$16") (pin "A") (pinfunction "A_A") (pintype "bidirectional"))
    )
    (net (code "37") (name "/LED10") (class "Default")
      (node (ref "IC8") (pin "5") (pinfunction "QC_5") (pintype "output"))
      (node (ref "U$15") (pin "A") (pinfunction "A_A") (pintype "bidirectional"))
    )
    (net (code "38") (name "/LED11") (class "Default")
      (node (ref "IC8") (pin "4") (pinfunction "QB_4") (pintype "output"))
      (node (ref "U$14") (pin "A") (pinfunction "A_A") (pintype "bidirectional"))
    )
    (net (code "39") (name "/LED_C") (class "Default")
      (node (ref "IC1") (pin "8") (pinfunction "CLK_8") (pintype "input"))
      (node (ref "IC10") (pin "26") (pinfunction "RC1/AN7/RPC1_26") (pintype "bidirectional"))
      (node (ref "IC8") (pin "8") (pinfunction "CLK_8") (pintype "input"))
      (node (ref "U1") (pin "17") (pinfunction "PIO1_9/CT16B1_MAT0/MOSI1_17") (pintype "bidirectional"))
    )
    (net (code "40") (name "/LED_S") (class "Default")
      (node (ref "IC1") (pin "1") (pinfunction "A_1") (pintype "input"))
      (node (ref "IC1") (pin "2") (pinfunction "B_2") (pintype "input"))
      (node (ref "IC10") (pin "25") (pinfunction "RC0/AN6/RPC0_25") (pintype "bidirectional"))
      (node (ref "U1") (pin "18") (pinfunction "PIO3_4/CT16B0_CAP1/RXD_18") (pintype "bidirectional"))
    )
    (net (code "41") (name "/MISO") (class "Default")
      (node (ref "IC10") (pin "20") (pinfunction "RA1/AN1/RPA1/VREF-/CVREF-/CTED2_20") (pintype "bidirectional"))
      (node (ref "IC2") (pin "14") (pinfunction "SO_14") (pintype "bidirectional"))
      (node (ref "U1") (pin "27") (pinfunction "PIO0_8/MISO0/CT16B0_MAT0_27") (pintype "bidirectional"))
    )
    (net (code "42") (name "/MOSI") (class "Default")
      (node (ref "IC10") (pin "9") (pinfunction "RB11/RPB11/PGEC2/PMD1_9") (pintype "bidirectional"))
      (node (ref "IC2") (pin "13") (pinfunction "SI_13") (pintype "bidirectional"))
      (node (ref "IC3") (pin "6") (pinfunction "SI_6") (pintype "bidirectional"))
      (node (ref "U$3") (pin "8") (pinfunction "MOSI_D_8") (pintype "bidirectional"))
      (node (ref "U1") (pin "28") (pinfunction "PIO0_9/MOSI0/CT16B0_MAT1_28") (pintype "bidirectional"))
    )
    (net (code "43") (name "/N$73") (class "Default")
      (node (ref "IC8") (pin "10") (pinfunction "QE_10") (pintype "output"))
    )
    (net (code "44") (name "/N$74") (class "Default")
      (node (ref "IC8") (pin "11") (pinfunction "QF_11") (pintype "output"))
    )
    (net (code "45") (name "/N$75") (class "Default")
      (node (ref "IC8") (pin "12") (pinfunction "QG_12") (pintype "output"))
    )
    (net (code "46") (name "/N$76") (class "Default")
      (node (ref "IC8") (pin "13") (pinfunction "QH_13") (pintype "output"))
    )
    (net (code "47") (name "/PD_CK") (class "Default")
      (node (ref "IC10") (pin "22") (pinfunction "RB1/AN3/RPB1/C1INC/C2INA/PGEC1/CTED12_22") (pintype "bidirectional"))
      (node (ref "JP6") (pin "3") (pinfunction "3_3") (pintype "passive"))
      (node (ref "U1") (pin "29") (pinfunction "SWCLK/PIO0_10/SCK0/CT16B0_MAT2_29") (pintype "bidirectional"))
    )
    (net (code "48") (name "/PD_DA") (class "Default")
      (node (ref "IC10") (pin "21") (pinfunction "RB0/AN2/RPB0/C1IND/C2INB/C3IND/PGED1_21") (pintype "bidirectional"))
      (node (ref "JP6") (pin "1") (pinfunction "1_1") (pintype "passive"))
      (node (ref "U1") (pin "39") (pinfunction "SWDIO/PIO1_3/AD4/CT32B1_MAT2_39") (pintype "bidirectional"))
    )
    (net (code "49") (name "/RST") (class "Default")
      (node (ref "JP6") (pin "2") (pinfunction "2_2") (pintype "passive"))
      (node (ref "JP7") (pin "1") (pinfunction "1_1") (pintype "passive"))
      (node (ref "JP8") (pin "1") (pinfunction "1_1") (pintype "passive"))
      (node (ref "R42") (pin "2") (pinfunction "2_2") (pintype "passive"))
    )
    (net (code "50") (name "/RX") (class "Default")
      (node (ref "IC10") (pin "24") (pinfunction "RB3/AN5/RPB3/C1INA/C2INC/RTCC/SCL2_24") (pintype "bidirectional"))
      (node (ref "U1") (pin "46") (pinfunction "PIO1_6/RXD/CT32B0_MAT0_46") (pintype "bidirectional"))
    )
    (net (code "51") (name "/SCK") (class "Default")
      (node (ref "IC10") (pin "14") (pinfunction "RB14/AN10/RPB14/CVREF/C3INB/SCK1/CTED5/PMWR_14") (pintype "bidirectional"))
      (node (ref "IC2") (pin "15") (pinfunction "SCK_15") (pintype "bidirectional"))
      (node (ref "IC3") (pin "7") (pinfunction "SCK_7") (pintype "bidirectional"))
      (node (ref "U$3") (pin "9") (pinfunction "SCK_D_9") (pintype "bidirectional"))
      (node (ref "U1") (pin "22") (pinfunction "PIO0_6/SCK0_22") (pintype "bidirectional"))
    )
    (net (code "52") (name "/SCL") (class "Default")
      (node (ref "IC10") (pin "44") (pinfunction "RB8/RPB8/SCL1/CTED10/PMD4_44") (pintype "bidirectional"))
      (node (ref "IC5") (pin "6") (pinfunction "SCL_6") (pintype "input"))
      (node (ref "JP10") (pin "2") (pinfunction "2_2") (pintype "passive"))
      (node (ref "R44") (pin "2") (pinfunction "2_2") (pintype "passive"))
      (node (ref "U$17") (pin "3") (pinfunction "SCL_3") (pintype "bidirectional"))
      (node (ref "U$18") (pin "4") (pinfunction "SCK_4") (pintype "bidirectional"))
      (node (ref "U$19") (pin "1") (pinfunction "SCL_1") (pintype "bidirectional"))
      (node (ref "U$34") (pin "14") (pinfunction "SCL/SPC_14") (pintype "input"))
      (node (ref "U1") (pin "15") (pinfunction "PIO0_4/SCL_15") (pintype "bidirectional"))
      (node (ref "U2") (pin "8") (pinfunction "SCL_8") (pintype "bidirectional"))
    )
    (net (code "53") (name "/SDA") (class "Default")
      (node (ref "IC10") (pin "1") (pinfunction "RB9/RPB9/SDA1/CTED4/PMD3_1") (pintype "bidirectional"))
      (node (ref "IC5") (pin "5") (pinfunction "SDA_5") (pintype "input"))
      (node (ref "JP10") (pin "1") (pinfunction "1_1") (pintype "passive"))
      (node (ref "R43") (pin "2") (pinfunction "2_2") (pintype "passive"))
      (node (ref "U$17") (pin "4") (pinfunction "SDA_4") (pintype "bidirectional"))
      (node (ref "U$18") (pin "5") (pinfunction "SDA_5") (pintype "bidirectional"))
      (node (ref "U$19") (pin "16") (pinfunction "SDA_16") (pintype "bidirectional"))
      (node (ref "U$34") (pin "13") (pinfunction "SDA/SDI_13") (pintype "bidirectional"))
      (node (ref "U1") (pin "16") (pinfunction "PIO0_5/SDA_16") (pintype "bidirectional"))
      (node (ref "U2") (pin "7") (pinfunction "SDA_7") (pintype "bidirectional"))
    )
    (net (code "54") (name "/TX") (class "Default")
      (node (ref "IC10") (pin "23") (pinfunction "RB2/AN4/RPB2/C1INB/C2IND/SDA2/CTED13_23") (pintype "bidirectional"))
      (node (ref "U1") (pin "47") (pinfunction "PIO1_7/TXD/CT32B0_MAT1_47") (pintype "bidirectional"))
    )
    (net (code "55") (name "GND") (class "Default")
      (node (ref "C1") (pin "2") (pinfunction "2_2") (pintype "passive"))
      (node (ref "C10") (pin "2") (pinfunction "2_2") (pintype "passive"))
      (node (ref "C11") (pin "1") (pinfunction "1_1") (pintype "passive"))
      (node (ref "C12") (pin "1") (pinfunction "1_1") (pintype "passive"))
      (node (ref "C13") (pin "1") (pinfunction "1_1") (pintype "passive"))
      (node (ref "C15") (pin "1") (pinfunction "1_1") (pintype "passive"))
      (node (ref "C16") (pin "1") (pinfunction "1_1") (pintype "passive"))
      (node (ref "C17") (pin "1") (pinfunction "1_1") (pintype "passive"))
      (node (ref "C18") (pin "1") (pinfunction "1_1") (pintype "passive"))
      (node (ref "C19") (pin "1") (pinfunction "1_1") (pintype "passive"))
      (node (ref "C20") (pin "1") (pinfunction "1_1") (pintype "passive"))
      (node (ref "C21") (pin "1") (pinfunction "1_1") (pintype "passive"))
      (node (ref "C22") (pin "1") (pinfunction "1_1") (pintype "passive"))
      (node (ref "C23") (pin "1") (pinfunction "1_1") (pintype "passive"))
      (node (ref "C24") (pin "1") (pinfunction "1_1") (pintype "passive"))
      (node (ref "C25") (pin "1") (pinfunction "1_1") (pintype "passive"))
      (node (ref "C26") (pin "1") (pinfunction "1_1") (pintype "passive"))
      (node (ref "C6") (pin "-") (pinfunction "-_-") (pintype "passive"))
      (node (ref "C7") (pin "-") (pinfunction "-_-") (pintype "passive"))
      (node (ref "C8") (pin "2") (pinfunction "2_2") (pintype "passive"))
      (node (ref "C9") (pin "2") (pinfunction "2_2") (pintype "passive"))
      (node (ref "D3") (pin "A") (pinfunction "A_A") (pintype "input"))
      (node (ref "IC1") (pin "7") (pinfunction "GND_7") (pintype "power_in"))
      (node (ref "IC10") (pin "16") (pinfunction "AVSS_16") (pintype "power_in"))
      (node (ref "IC10") (pin "29") (pinfunction "VSS_29") (pintype "power_in"))
      (node (ref "IC10") (pin "39") (pinfunction "VSS2_39") (pintype "power_in"))
      (node (ref "IC10") (pin "6") (pinfunction "VSS1_6") (pintype "power_in"))
      (node (ref "IC2") (pin "11") (pinfunction "VSS_11") (pintype "power_in"))
      (node (ref "IC3") (pin "4") (pinfunction "VSS_4") (pintype "power_in"))
      (node (ref "IC4") (pin "4") (pinfunction "VSS_4") (pintype "power_in"))
      (node (ref "IC5") (pin "4") (pinfunction "VSS_4") (pintype "power_in"))
      (node (ref "IC5") (pin "7") (pinfunction "WP_7") (pintype "input"))
      (node (ref "IC6") (pin "1") (pinfunction "VSS_1") (pintype "input"))
      (node (ref "IC7") (pin "1") (pinfunction "GND_1") (pintype "power_in"))
      (node (ref "IC7") (pin "6") (pinfunction "THR_6") (pintype "input"))
      (node (ref "IC8") (pin "7") (pinfunction "GND_7") (pintype "power_in"))
      (node (ref "IC9") (pin "1") (pinfunction "P8_1") (pintype "input"))
      (node (ref "IC9") (pin "11") (pinfunction "SI_11") (pintype "input"))
      (node (ref "IC9") (pin "8") (pinfunction "VSS_8") (pintype "power_in"))
      (node (ref "JP10") (pin "4") (pinfunction "4_4") (pintype "passive"))
      (node (ref "JP3") (pin "1") (pinfunction "1_1") (pintype "passive"))
      (node (ref "JP4") (pin "1") (pinfunction "1_1") (pintype "passive"))
      (node (ref "JP5") (pin "8") (pinfunction "8_8") (pintype "passive"))
      (node (ref "JP6") (pin "5") (pinfunction "5_5") (pintype "passive"))
      (node (ref "JP7") (pin "3") (pinfunction "3_3") (pintype "passive"))
      (node (ref "JP8") (pin "3") (pinfunction "3_3") (pintype "passive"))
      (node (ref "JP9") (pin "1") (pinfunction "1_1") (pintype "passive"))
      (node (ref "K1") (pin "2B") (pinfunction "2B_2B") (pintype "bidirectional"))
      (node (ref "K2") (pin "2B") (pinfunction "2B_2B") (pintype "bidirectional"))
      (node (ref "K3") (pin "2B") (pinfunction "2B_2B") (pintype "bidirectional"))
      (node (ref "K4") (pin "2B") (pinfunction "2B_2B") (pintype "bidirectional"))
      (node (ref "K5") (pin "2B") (pinfunction "2B_2B") (pintype "bidirectional"))
      (node (ref "R10") (pin "2") (pinfunction "2_2") (pintype "passive"))
      (node (ref "R11") (pin "2") (pinfunction "2_2") (pintype "passive"))
      (node (ref "R12") (pin "2") (pinfunction "2_2") (pintype "passive"))
      (node (ref "R21") (pin "1") (pinfunction "1_1") (pintype "passive"))
      (node (ref "R26") (pin "2") (pinfunction "2_2") (pintype "passive"))
      (node (ref "R27") (pin "2") (pinfunction "2_2") (pintype "passive"))
      (node (ref "R28") (pin "2") (pinfunction "2_2") (pintype "passive"))
      (node (ref "R31") (pin "2") (pinfunction "2_2") (pintype "passive"))
      (node (ref "R33") (pin "1") (pinfunction "1_1") (pintype "passive"))
      (node (ref "R36") (pin "1") (pinfunction "1_1") (pintype "passive"))
      (node (ref "R40") (pin "1") (pinfunction "1_1") (pintype "passive"))
      (node (ref "R9") (pin "2") (pinfunction "2_2") (pintype "passive"))
      (node (ref "T3") (pin "2") (pinfunction "E_2") (pintype "passive"))
      (node (ref "T4") (pin "2") (pinfunction "E_2") (pintype "passive"))
      (node (ref "T5") (pin "2") (pinfunction "E_2") (pintype "passive"))
      (node (ref "U$10") (pin "C") (pinfunction "C_C") (pintype "bidirectional"))
      (node (ref "U$17") (pin "2") (pinfunction "GND_2") (pintype "bidirectional"))
      (node (ref "U$18") (pin "2") (pinfunction "GND_2") (pintype "bidirectional"))
      (node (ref "U$19") (pin "11") (pinfunction "GND_11") (pintype "bidirectional"))
      (node (ref "U$19") (pin "9") (pinfunction "GND_9") (pintype "bidirectional"))
      (node (ref "U$2") (pin "C") (pinfunction "C_C") (pintype "bidirectional"))
      (node (ref "U$21") (pin "1") (pinfunction "VSS_1") (pintype "bidirectional"))
      (node (ref "U$22") (pin "1") (pinfunction "VSS_1") (pintype "bidirectional"))
      (node (ref "U$3") (pin "1") (pinfunction "GND_1") (pintype "bidirectional"))
      (node (ref "U$3") (pin "16") (pinfunction "LED-_16") (pintype "bidirectional"))
      (node (ref "U$34") (pin "2") (pinfunction "GND_2") (pintype "power_in"))
      (node (ref "U$34") (pin "4") (pinfunction "IADDR0_4") (pintype "input"))
      (node (ref "U$34") (pin "5") (pinfunction "GND_5") (pintype "power_in"))
      (node (ref "U$4") (pin "C") (pinfunction "C_C") (pintype "bidirectional"))
      (node (ref "U$5") (pin "C") (pinfunction "C_C") (pintype "bidirectional"))
      (node (ref "U$6") (pin "C") (pinfunction "C_C") (pintype "bidirectional"))
      (node (ref "U$7") (pin "C") (pinfunction "C_C") (pintype "bidirectional"))
      (node (ref "U$8") (pin "C") (pinfunction "C_C") (pintype "bidirectional"))
      (node (ref "U$9") (pin "C") (pinfunction "C_C") (pintype "bidirectional"))
      (node (ref "U1") (pin "41") (pinfunction "VSS(IO)_41") (pintype "power_in"))
      (node (ref "U1") (pin "5") (pinfunction "VSS_5") (pintype "power_in"))
      (node (ref "U2") (pin "3") (pinfunction "GND_3") (pintype "power_in"))
    )
    (net (code "56") (name "Net-(C2-Pad1)") (class "Default")
      (node (ref "C2") (pin "1") (pinfunction "1_1") (pintype "passive"))
      (node (ref "JP4") (pin "2") (pinfunction "2_2") (pintype "passive"))
      (node (ref "R38") (pin "2") (pinfunction "2_2") (pintype "passive"))
    )
    (net (code "57") (name "Net-(C3-Pad1)") (class "Default")
      (node (ref "C3") (pin "1") (pinfunction "1_1") (pintype "passive"))
      (node (ref "JP3") (pin "2") (pinfunction "2_2") (pintype "passive"))
    )
    (net (code "58") (name "Net-(C9-Pad1)") (class "Default")
      (node (ref "C9") (pin "1") (pinfunction "1_1") (pintype "passive"))
      (node (ref "D2") (pin "K") (pinfunction "K_K") (pintype "output"))
      (node (ref "R39") (pin "1") (pinfunction "1_1") (pintype "passive"))
    )
    (net (code "59") (name "Net-(C10-Pad1)") (class "Default")
      (node (ref "C10") (pin "1") (pinfunction "1_1") (pintype "passive"))
      (node (ref "JP1") (pin "1") (pinfunction "1_1") (pintype "passive"))
      (node (ref "R39") (pin "2") (pinfunction "2_2") (pintype "passive"))
    )
    (net (code "60") (name "Net-(D1-PadK)") (class "Default")
      (node (ref "D1") (pin "K") (pinfunction "K_K") (pintype "output"))
      (node (ref "R34") (pin "1") (pinfunction "1_1") (pintype "passive"))
    )
    (net (code "61") (name "Net-(IC2-CH0)") (class "Default")
      (node (ref "C2") (pin "2") (pinfunction "2_2") (pintype "passive"))
      (node (ref "IC2") (pin "2") (pinfunction "CH0_2") (pintype "bidirectional"))
      (node (ref "R22") (pin "2") (pinfunction "2_2") (pintype "passive"))
    )
    (net (code "62") (name "Net-(IC2-CH1)") (class "Default")
      (node (ref "C3") (pin "2") (pinfunction "2_2") (pintype "passive"))
      (node (ref "IC2") (pin "3") (pinfunction "CH1_3") (pintype "bidirectional"))
      (node (ref "R23") (pin "2") (pinfunction "2_2") (pintype "passive"))
    )
    (net (code "63") (name "Net-(IC2-CH2)") (class "Default")
      (node (ref "C4") (pin "2") (pinfunction "2_2") (pintype "passive"))
      (node (ref "IC2") (pin "4") (pinfunction "CH2_4") (pintype "bidirectional"))
      (node (ref "R24") (pin "2") (pinfunction "2_2") (pintype "passive"))
    )
    (net (code "64") (name "Net-(IC2-CH3)") (class "Default")
      (node (ref "C5") (pin "2") (pinfunction "2_2") (pintype "passive"))
      (node (ref "IC2") (pin "5") (pinfunction "CH3_5") (pintype "bidirectional"))
      (node (ref "R25") (pin "2") (pinfunction "2_2") (pintype "passive"))
    )
    (net (code "65") (name "Net-(IC2-VOUT)") (class "Default")
      (node (ref "IC2") (pin "1") (pinfunction "VOUT_1") (pintype "bidirectional"))
      (node (ref "IC3") (pin "2") (pinfunction "CH0_2") (pintype "bidirectional"))
    )
    (net (code "66") (name "Net-(IC2-VREF)") (class "Default")
      (node (ref "IC2") (pin "10") (pinfunction "VREF_10") (pintype "bidirectional"))
      (node (ref "IC3") (pin "3") (pinfunction "VREF_3") (pintype "bidirectional"))
      (node (ref "R29") (pin "1") (pinfunction "1_1") (pintype "passive"))
    )
    (net (code "67") (name "Net-(IC4A-IN-)") (class "Default")
      (node (ref "IC4") (pin "1") (pinfunction "VYSTUP_1") (pintype "output"))
      (node (ref "IC4") (pin "2") (pinfunction "IN-_2") (pintype "input"))
      (node (ref "R22") (pin "1") (pinfunction "1_1") (pintype "passive"))
      (node (ref "R23") (pin "1") (pinfunction "1_1") (pintype "passive"))
      (node (ref "R24") (pin "1") (pinfunction "1_1") (pintype "passive"))
      (node (ref "R25") (pin "1") (pinfunction "1_1") (pintype "passive"))
      (node (ref "R29") (pin "2") (pinfunction "2_2") (pintype "passive"))
    )
    (net (code "68") (name "Net-(IC4A-NEIN+)") (class "Default")
      (node (ref "C1") (pin "1") (pinfunction "1_1") (pintype "passive"))
      (node (ref "IC4") (pin "3") (pinfunction "NEIN+_3") (pintype "input"))
      (node (ref "R20") (pin "1") (pinfunction "1_1") (pintype "passive"))
      (node (ref "R21") (pin "2") (pinfunction "2_2") (pintype "passive"))
    )
    (net (code "69") (name "Net-(IC4B-NEIN+)") (class "Default")
      (node (ref "IC4") (pin "5") (pinfunction "NEIN+_5") (pintype "input"))
      (node (ref "R30") (pin "1") (pinfunction "1_1") (pintype "passive"))
      (node (ref "R31") (pin "1") (pinfunction "1_1") (pintype "passive"))
    )
    (net (code "70") (name "Net-(IC7-DIS)") (class "Default")
      (node (ref "IC7") (pin "7") (pinfunction "DIS_7") (pintype "input"))
      (node (ref "R32") (pin "2") (pinfunction "2_2") (pintype "passive"))
      (node (ref "T2") (pin "1") (pinfunction "B_1") (pintype "passive"))
    )
    (net (code "71") (name "Net-(IC7-Q)") (class "Default")
      (node (ref "D1") (pin "A") (pinfunction "A_A") (pintype "input"))
      (node (ref "IC7") (pin "3") (pinfunction "Q_3") (pintype "output"))
      (node (ref "R32") (pin "1") (pinfunction "1_1") (pintype "passive"))
    )
    (net (code "72") (name "Net-(IC7-R)") (class "Default")
      (node (ref "IC7") (pin "4") (pinfunction "R_4") (pintype "input"))
      (node (ref "R35") (pin "2") (pinfunction "2_2") (pintype "passive"))
      (node (ref "T4") (pin "3") (pinfunction "C_3") (pintype "passive"))
      (node (ref "T5") (pin "3") (pinfunction "C_3") (pintype "passive"))
    )
    (net (code "73") (name "Net-(IC7-TR)") (class "Default")
      (node (ref "C8") (pin "1") (pinfunction "1_1") (pintype "passive"))
      (node (ref "IC7") (pin "2") (pinfunction "TR_2") (pintype "input"))
      (node (ref "R33") (pin "2") (pinfunction "2_2") (pintype "passive"))
      (node (ref "R34") (pin "2") (pinfunction "2_2") (pintype "passive"))
    )
    (net (code "74") (name "Net-(IC10-VCAP)") (class "Default")
      (node (ref "C24") (pin "2") (pinfunction "2_2") (pintype "passive"))
      (node (ref "IC10") (pin "7") (pinfunction "VCAP_7") (pintype "bidirectional"))
    )
    (net (code "75") (name "Net-(IC10-~{MCLR})") (class "Default")
      (node (ref "IC10") (pin "18") (pinfunction "~{MCLR}_18") (pintype "bidirectional"))
      (node (ref "JP8") (pin "2") (pinfunction "2_2") (pintype "passive"))
    )
    (net (code "76") (name "Net-(JP2-Pad1)") (class "Default")
      (node (ref "JP2") (pin "1") (pinfunction "1_1") (pintype "passive"))
      (node (ref "R40") (pin "2") (pinfunction "2_2") (pintype "passive"))
      (node (ref "R41") (pin "1") (pinfunction "1_1") (pintype "passive"))
    )
    (net (code "77") (name "Net-(R1-Pad2)") (class "Default")
      (node (ref "R1") (pin "2") (pinfunction "2_2") (pintype "passive"))
      (node (ref "U$2") (pin "A") (pinfunction "A_A") (pintype "bidirectional"))
    )
    (net (code "78") (name "Net-(R2-Pad2)") (class "Default")
      (node (ref "R2") (pin "2") (pinfunction "2_2") (pintype "passive"))
      (node (ref "U$4") (pin "A") (pinfunction "A_A") (pintype "bidirectional"))
    )
    (net (code "79") (name "Net-(R3-Pad2)") (class "Default")
      (node (ref "R3") (pin "2") (pinfunction "2_2") (pintype "passive"))
      (node (ref "U$5") (pin "A") (pinfunction "A_A") (pintype "bidirectional"))
    )
    (net (code "80") (name "Net-(R4-Pad2)") (class "Default")
      (node (ref "R4") (pin "2") (pinfunction "2_2") (pintype "passive"))
      (node (ref "U$6") (pin "A") (pinfunction "A_A") (pintype "bidirectional"))
    )
    (net (code "81") (name "Net-(R5-Pad2)") (class "Default")
      (node (ref "R5") (pin "2") (pinfunction "2_2") (pintype "passive"))
      (node (ref "U$7") (pin "A") (pinfunction "A_A") (pintype "bidirectional"))
    )
    (net (code "82") (name "Net-(R6-Pad2)") (class "Default")
      (node (ref "R6") (pin "2") (pinfunction "2_2") (pintype "passive"))
      (node (ref "U$8") (pin "A") (pinfunction "A_A") (pintype "bidirectional"))
    )
    (net (code "83") (name "Net-(R7-Pad2)") (class "Default")
      (node (ref "R7") (pin "2") (pinfunction "2_2") (pintype "passive"))
      (node (ref "U$9") (pin "A") (pinfunction "A_A") (pintype "bidirectional"))
    )
    (net (code "84") (name "Net-(R8-Pad2)") (class "Default")
      (node (ref "R8") (pin "2") (pinfunction "2_2") (pintype "passive"))
      (node (ref "U$10") (pin "A") (pinfunction "A_A") (pintype "bidirectional"))
    )
    (net (code "85") (name "Net-(R9-Pad1)") (class "Default")
      (node (ref "R9") (pin "1") (pinfunction "1_1") (pintype "passive"))
      (node (ref "U$13") (pin "C") (pinfunction "C_C") (pintype "bidirectional"))
    )
    (net (code "86") (name "Net-(R10-Pad1)") (class "Default")
      (node (ref "R10") (pin "1") (pinfunction "1_1") (pintype "passive"))
      (node (ref "U$1") (pin "C") (pinfunction "C_C") (pintype "bidirectional"))
    )
    (net (code "87") (name "Net-(R11-Pad1)") (class "Default")
      (node (ref "R11") (pin "1") (pinfunction "1_1") (pintype "passive"))
      (node (ref "U$11") (pin "C") (pinfunction "C_C") (pintype "bidirectional"))
    )
    (net (code "88") (name "Net-(R12-Pad1)") (class "Default")
      (node (ref "R12") (pin "1") (pinfunction "1_1") (pintype "passive"))
      (node (ref "U$12") (pin "C") (pinfunction "C_C") (pintype "bidirectional"))
    )
    (net (code "89") (name "Net-(R26-Pad1)") (class "Default")
      (node (ref "R26") (pin "1") (pinfunction "1_1") (pintype "passive"))
      (node (ref "U$14") (pin "C") (pinfunction "C_C") (pintype "bidirectional"))
    )
    (net (code "90") (name "Net-(R27-Pad1)") (class "Default")
      (node (ref "R27") (pin "1") (pinfunction "1_1") (pintype "passive"))
      (node (ref "U$15") (pin "C") (pinfunction "C_C") (pintype "bidirectional"))
    )
    (net (code "91") (name "Net-(R28-Pad1)") (class "Default")
      (node (ref "R28") (pin "1") (pinfunction "1_1") (pintype "passive"))
      (node (ref "U$16") (pin "C") (pinfunction "C_C") (pintype "bidirectional"))
    )
    (net (code "92") (name "Net-(T1-B)") (class "Default")
      (node (ref "R19") (pin "2") (pinfunction "2_2") (pintype "passive"))
      (node (ref "T1") (pin "1") (pinfunction "B_1") (pintype "passive"))
    )
    (net (code "93") (name "Net-(T1-E)") (class "Default")
      (node (ref "R18") (pin "1") (pinfunction "1_1") (pintype "passive"))
      (node (ref "T1") (pin "2") (pinfunction "E_2") (pintype "passive"))
    )
    (net (code "94") (name "Net-(T2-C)") (class "Default")
      (node (ref "D2") (pin "A") (pinfunction "A_A") (pintype "input"))
      (node (ref "T2") (pin "3") (pinfunction "C_3") (pintype "passive"))
      (node (ref "U$20") (pin "P$2") (pinfunction "P$2_P$2") (pintype "bidirectional"))
    )
    (net (code "95") (name "Net-(T2-E)") (class "Default")
      (node (ref "R36") (pin "2") (pinfunction "2_2") (pintype "passive"))
      (node (ref "T2") (pin "2") (pinfunction "E_2") (pintype "passive"))
      (node (ref "T5") (pin "1") (pinfunction "B_1") (pintype "passive"))
    )
    (net (code "96") (name "Net-(T3-B)") (class "Default")
      (node (ref "D3") (pin "K") (pinfunction "K_K") (pintype "output"))
      (node (ref "R41") (pin "2") (pinfunction "2_2") (pintype "passive"))
      (node (ref "T3") (pin "1") (pinfunction "B_1") (pintype "passive"))
    )
    (net (code "97") (name "Net-(T4-B)") (class "Default")
      (node (ref "R37") (pin "2") (pinfunction "2_2") (pintype "passive"))
      (node (ref "T4") (pin "1") (pinfunction "B_1") (pintype "passive"))
    )
    (net (code "98") (name "Net-(U$3-LED+)") (class "Default")
      (node (ref "R18") (pin "2") (pinfunction "2_2") (pintype "passive"))
      (node (ref "U$3") (pin "15") (pinfunction "LED+_15") (pintype "bidirectional"))
    )
    (net (code "99") (name "Net-(U$17-VCORE)") (class "Default")
      (node (ref "C11") (pin "2") (pinfunction "2_2") (pintype "passive"))
      (node (ref "U$17") (pin "1") (pinfunction "VCORE_1") (pintype "bidirectional"))
    )
    (net (code "100") (name "Net-(U$19-C1)") (class "Default")
      (node (ref "C13") (pin "2") (pinfunction "2_2") (pintype "passive"))
      (node (ref "U$19") (pin "10") (pinfunction "C1_10") (pintype "bidirectional"))
    )
    (net (code "101") (name "Net-(U$19-SETC)") (class "Default")
      (node (ref "C14") (pin "2") (pinfunction "2_2") (pintype "passive"))
      (node (ref "U$19") (pin "12") (pinfunction "SETC_12") (pintype "bidirectional"))
    )
    (net (code "102") (name "Net-(U$19-SETP)") (class "Default")
      (node (ref "C14") (pin "1") (pinfunction "1_1") (pintype "passive"))
      (node (ref "U$19") (pin "8") (pinfunction "SETP_8") (pintype "bidirectional"))
    )
    (net (code "103") (name "Net-(U$21-OUT)") (class "Default")
      (node (ref "C5") (pin "1") (pinfunction "1_1") (pintype "passive"))
      (node (ref "U$21") (pin "3") (pinfunction "OUT_3") (pintype "bidirectional"))
    )
    (net (code "104") (name "Net-(U$22-OUT)") (class "Default")
      (node (ref "C4") (pin "1") (pinfunction "1_1") (pintype "passive"))
      (node (ref "U$22") (pin "3") (pinfunction "OUT_3") (pintype "bidirectional"))
    )
    (net (code "105") (name "Net-(U1-RESET{slash}PIO0_0)") (class "Default")
      (node (ref "JP7") (pin "2") (pinfunction "2_2") (pintype "passive"))
      (node (ref "U1") (pin "3") (pinfunction "RESET/PIO0_0_3") (pintype "bidirectional"))
    )
    (net (code "106") (name "Net-(U2-CAP)") (class "Default")
      (node (ref "C12") (pin "2") (pinfunction "2_2") (pintype "passive"))
      (node (ref "U2") (pin "2") (pinfunction "CAP_2") (pintype "power_in"))
    )
    (net (code "107") (name "unconnected-(IC2-CH4-Pad6)") (class "Default")
      (node (ref "IC2") (pin "6") (pinfunction "CH4_6") (pintype "bidirectional"))
    )
    (net (code "108") (name "unconnected-(IC2-CH5-Pad7)") (class "Default")
      (node (ref "IC2") (pin "7") (pinfunction "CH5_7") (pintype "bidirectional"))
    )
    (net (code "109") (name "unconnected-(IC2-CH6-Pad8)") (class "Default")
      (node (ref "IC2") (pin "8") (pinfunction "CH6_8") (pintype "bidirectional"))
    )
    (net (code "110") (name "unconnected-(IC2-CH7-Pad9)") (class "Default")
      (node (ref "IC2") (pin "9") (pinfunction "CH7_9") (pintype "bidirectional"))
    )
    (net (code "111") (name "unconnected-(IC7-CV-Pad5)") (class "Default")
      (node (ref "IC7") (pin "5") (pinfunction "CV_5") (pintype "input"))
    )
    (net (code "112") (name "unconnected-(IC9A-Q6-Pad2)") (class "Default")
      (node (ref "IC9") (pin "2") (pinfunction "Q6_2") (pintype "output"))
    )
    (net (code "113") (name "unconnected-(IC9A-Q8-Pad3)") (class "Default")
      (node (ref "IC9") (pin "3") (pinfunction "Q8_3") (pintype "output"))
    )
    (net (code "114") (name "unconnected-(IC10-RA7{slash}TCK{slash}PGEC{slash}CTED8{slash}PMA7-Pad13)") (class "Default")
      (node (ref "IC10") (pin "13") (pinfunction "RA7/TCK/PGEC/CTED8/PMA7_13") (pintype "bidirectional"))
    )
    (net (code "115") (name "unconnected-(IC10-RB6{slash}RPB6{slash}PGEC3{slash}PMD6-Pad42)") (class "Default")
      (node (ref "IC10") (pin "42") (pinfunction "RB6/RPB6/PGEC3/PMD6_42") (pintype "bidirectional"))
    )
    (net (code "116") (name "unconnected-(IC10-RB7{slash}RPB7{slash}INT0{slash}CTED3{slash}PMD5-Pad43)") (class "Default")
      (node (ref "IC10") (pin "43") (pinfunction "RB7/RPB7/INT0/CTED3/PMD5_43") (pintype "bidirectional"))
    )
    (net (code "117") (name "unconnected-(IC10-RB10{slash}RPB10{slash}CTED11{slash}PGED2{slash}PMD2-Pad8)") (class "Default")
      (node (ref "IC10") (pin "8") (pinfunction "RB10/RPB10/CTED11/PGED2/PMD2_8") (pintype "bidirectional"))
    )
    (net (code "118") (name "unconnected-(IC10-RC8{slash}RPC8{slash}PMA5-Pad4)") (class "Default")
      (node (ref "IC10") (pin "4") (pinfunction "RC8/RPC8/PMA5_4") (pintype "bidirectional"))
    )
    (net (code "119") (name "unconnected-(IC10-RC9{slash}RPC9{slash}CTED7{slash}PMA6-Pad5)") (class "Default")
      (node (ref "IC10") (pin "5") (pinfunction "RC9/RPC9/CTED7/PMA6_5") (pintype "bidirectional"))
    )
    (net (code "120") (name "unconnected-(K1-Pad1B)") (class "Default")
      (node (ref "K1") (pin "1B") (pinfunction "1B_1B") (pintype "bidirectional"))
    )
    (net (code "121") (name "unconnected-(K1-Pad2A)") (class "Default")
      (node (ref "K1") (pin "2A") (pinfunction "2A_2A") (pintype "bidirectional"))
    )
    (net (code "122") (name "unconnected-(K2-Pad1B)") (class "Default")
      (node (ref "K2") (pin "1B") (pinfunction "1B_1B") (pintype "bidirectional"))
    )
    (net (code "123") (name "unconnected-(K2-Pad2A)") (class "Default")
      (node (ref "K2") (pin "2A") (pinfunction "2A_2A") (pintype "bidirectional"))
    )
    (net (code "124") (name "unconnected-(K3-Pad1B)") (class "Default")
      (node (ref "K3") (pin "1B") (pinfunction "1B_1B") (pintype "bidirectional"))
    )
    (net (code "125") (name "unconnected-(K3-Pad2A)") (class "Default")
      (node (ref "K3") (pin "2A") (pinfunction "2A_2A") (pintype "bidirectional"))
    )
    (net (code "126") (name "unconnected-(K4-Pad1B)") (class "Default")
      (node (ref "K4") (pin "1B") (pinfunction "1B_1B") (pintype "bidirectional"))
    )
    (net (code "127") (name "unconnected-(K4-Pad2A)") (class "Default")
      (node (ref "K4") (pin "2A") (pinfunction "2A_2A") (pintype "bidirectional"))
    )
    (net (code "128") (name "unconnected-(K5-Pad1B)") (class "Default")
      (node (ref "K5") (pin "1B") (pinfunction "1B_1B") (pintype "bidirectional"))
    )
    (net (code "129") (name "unconnected-(K5-Pad2A)") (class "Default")
      (node (ref "K5") (pin "2A") (pinfunction "2A_2A") (pintype "bidirectional"))
    )
    (net (code "130") (name "unconnected-(U$3-CS_SD-Pad14)") (class "Default")
      (node (ref "U$3") (pin "14") (pinfunction "CS_SD_14") (pintype "bidirectional"))
    )
    (net (code "131") (name "unconnected-(U$3-MISO-Pad12)") (class "Default")
      (node (ref "U$3") (pin "12") (pinfunction "MISO_12") (pintype "bidirectional"))
    )
    (net (code "132") (name "unconnected-(U$3-MOSI-Pad13)") (class "Default")
      (node (ref "U$3") (pin "13") (pinfunction "MOSI_13") (pintype "bidirectional"))
    )
    (net (code "133") (name "unconnected-(U$3-NC1-Pad3)") (class "Default")
      (node (ref "U$3") (pin "3") (pinfunction "NC1_3") (pintype "bidirectional"))
    )
    (net (code "134") (name "unconnected-(U$3-NC2-Pad4)") (class "Default")
      (node (ref "U$3") (pin "4") (pinfunction "NC2_4") (pintype "bidirectional"))
    )
    (net (code "135") (name "unconnected-(U$3-NC3-Pad5)") (class "Default")
      (node (ref "U$3") (pin "5") (pinfunction "NC3_5") (pintype "bidirectional"))
    )
    (net (code "136") (name "unconnected-(U$3-SCK_SD-Pad11)") (class "Default")
      (node (ref "U$3") (pin "11") (pinfunction "SCK_SD_11") (pintype "bidirectional"))
    )
    (net (code "137") (name "unconnected-(U$17-ALH-Pad5)") (class "Default")
      (node (ref "U$17") (pin "5") (pinfunction "ALH_5") (pintype "bidirectional"))
    )
    (net (code "138") (name "unconnected-(U$17-ALL-Pad6)") (class "Default")
      (node (ref "U$17") (pin "6") (pinfunction "ALL_6") (pintype "bidirectional"))
    )
    (net (code "139") (name "unconnected-(U$17-NC-Pad7)") (class "Default")
      (node (ref "U$17") (pin "7") (pinfunction "NC_7") (pintype "bidirectional"))
    )
    (net (code "140") (name "unconnected-(U$18-ALT-Pad3)") (class "Default")
      (node (ref "U$18") (pin "3") (pinfunction "ALT_3") (pintype "bidirectional"))
    )
    (net (code "141") (name "unconnected-(U$19-DRDY-Pad15)") (class "Default")
      (node (ref "U$19") (pin "15") (pinfunction "DRDY_15") (pintype "bidirectional"))
    )
    (net (code "142") (name "unconnected-(U$19-NC-Pad3)") (class "Default")
      (node (ref "U$19") (pin "3") (pinfunction "NC_3") (pintype "bidirectional"))
    )
    (net (code "143") (name "unconnected-(U$19-NC-Pad5)") (class "Default")
      (node (ref "U$19") (pin "5") (pinfunction "NC_5") (pintype "bidirectional"))
    )
    (net (code "144") (name "unconnected-(U$19-NC-Pad6)") (class "Default")
      (node (ref "U$19") (pin "6") (pinfunction "NC_6") (pintype "bidirectional"))
    )
    (net (code "145") (name "unconnected-(U$19-NC-Pad7)") (class "Default")
      (node (ref "U$19") (pin "7") (pinfunction "NC_7") (pintype "bidirectional"))
    )
    (net (code "146") (name "unconnected-(U$19-NC-Pad14)") (class "Default")
      (node (ref "U$19") (pin "14") (pinfunction "NC_14") (pintype "bidirectional"))
    )
    (net (code "147") (name "unconnected-(U$34-INT1{slash}DRDY-Pad8)") (class "Default")
      (node (ref "U$34") (pin "8") (pinfunction "INT1/DRDY_8") (pintype "bidirectional"))
    )
    (net (code "148") (name "unconnected-(U$34-INT2-Pad9)") (class "Default")
      (node (ref "U$34") (pin "9") (pinfunction "INT2_9") (pintype "bidirectional"))
    )
    (net (code "149") (name "unconnected-(U$34-SDO-Pad12)") (class "Default")
      (node (ref "U$34") (pin "12") (pinfunction "SDO_12") (pintype "output"))
    )
    (net (code "150") (name "unconnected-(U1-PIO1_5{slash}RTS{slash}CT32B0_CAP0-Pad45)") (class "Default")
      (node (ref "U1") (pin "45") (pinfunction "PIO1_5/RTS/CT32B0_CAP0_45") (pintype "bidirectional"))
    )
    (net (code "151") (name "unconnected-(U1-PIO2_2{slash}DCD{slash}MISO1-Pad26)") (class "Default")
      (node (ref "U1") (pin "26") (pinfunction "PIO2_2/DCD/MISO1_26") (pintype "bidirectional"))
    )
    (net (code "152") (name "unconnected-(U1-PIO2_3{slash}RI{slash}MOSI1-Pad38)") (class "Default")
      (node (ref "U1") (pin "38") (pinfunction "PIO2_3/RI/MOSI1_38") (pintype "bidirectional"))
    )
    (net (code "153") (name "unconnected-(U1-PIO2_4{slash}CT16B1_MAT1{slash}SSEL1-Pad19)") (class "Default")
      (node (ref "U1") (pin "19") (pinfunction "PIO2_4/CT16B1_MAT1/SSEL1_19") (pintype "bidirectional"))
    )
    (net (code "154") (name "unconnected-(U1-PIO2_5{slash}CT32B0_MAT0-Pad20)") (class "Default")
      (node (ref "U1") (pin "20") (pinfunction "PIO2_5/CT32B0_MAT0_20") (pintype "bidirectional"))
    )
    (net (code "155") (name "unconnected-(U1-PIO2_10-Pad25)") (class "Default")
      (node (ref "U1") (pin "25") (pinfunction "PIO2_10_25") (pintype "bidirectional"))
    )
    (net (code "156") (name "unconnected-(U1-PIO3_0{slash}DTR{slash}CT16B0_MAT0{slash}TXD-Pad36)") (class "Default")
      (node (ref "U1") (pin "36") (pinfunction "PIO3_0/DTR/CT16B0_MAT0/TXD_36") (pintype "bidirectional"))
    )
    (net (code "157") (name "unconnected-(U1-PIO3_1{slash}DSR{slash}CT16B0_MAT1{slash}RXD-Pad37)") (class "Default")
      (node (ref "U1") (pin "37") (pinfunction "PIO3_1/DSR/CT16B0_MAT1/RXD_37") (pintype "bidirectional"))
    )
    (net (code "158") (name "unconnected-(U1-PIO3_2{slash}DCD{slash}CT16B0_MAT2{slash}SCK1-Pad43)") (class "Default")
      (node (ref "U1") (pin "43") (pinfunction "PIO3_2/DCD/CT16B0_MAT2/SCK1_43") (pintype "bidirectional"))
    )
    (net (code "159") (name "unconnected-(U1-PIO3_3{slash}RI{slash}CT16B0_CAP0-Pad48)") (class "Default")
      (node (ref "U1") (pin "48") (pinfunction "PIO3_3/RI/CT16B0_CAP0_48") (pintype "bidirectional"))
    )
    (net (code "160") (name "unconnected-(U1-PIO3_5{slash}CT16B1_CAP1{slash}TXD-Pad21)") (class "Default")
      (node (ref "U1") (pin "21") (pinfunction "PIO3_5/CT16B1_CAP1/TXD_21") (pintype "bidirectional"))
    )
    (net (code "161") (name "unconnected-(U1-XTALIN-Pad6)") (class "Default")
      (node (ref "U1") (pin "6") (pinfunction "XTALIN_6") (pintype "input"))
    )
    (net (code "162") (name "unconnected-(U1-XTALOUT-Pad7)") (class "Default")
      (node (ref "U1") (pin "7") (pinfunction "XTALOUT_7") (pintype "output"))
    )
    (net (code "163") (name "unconnected-(U2-INT1-Pad6)") (class "Default")
      (node (ref "U2") (pin "6") (pinfunction "INT1_6") (pintype "output"))
    )
    (net (code "164") (name "unconnected-(U2-INT2-Pad5)") (class "Default")
      (node (ref "U2") (pin "5") (pinfunction "INT2_5") (pintype "output"))
    )
  )
)
